# Meshtastic-DIY_v2.net
KiCad netlist of a schematic drawn in EAGLE
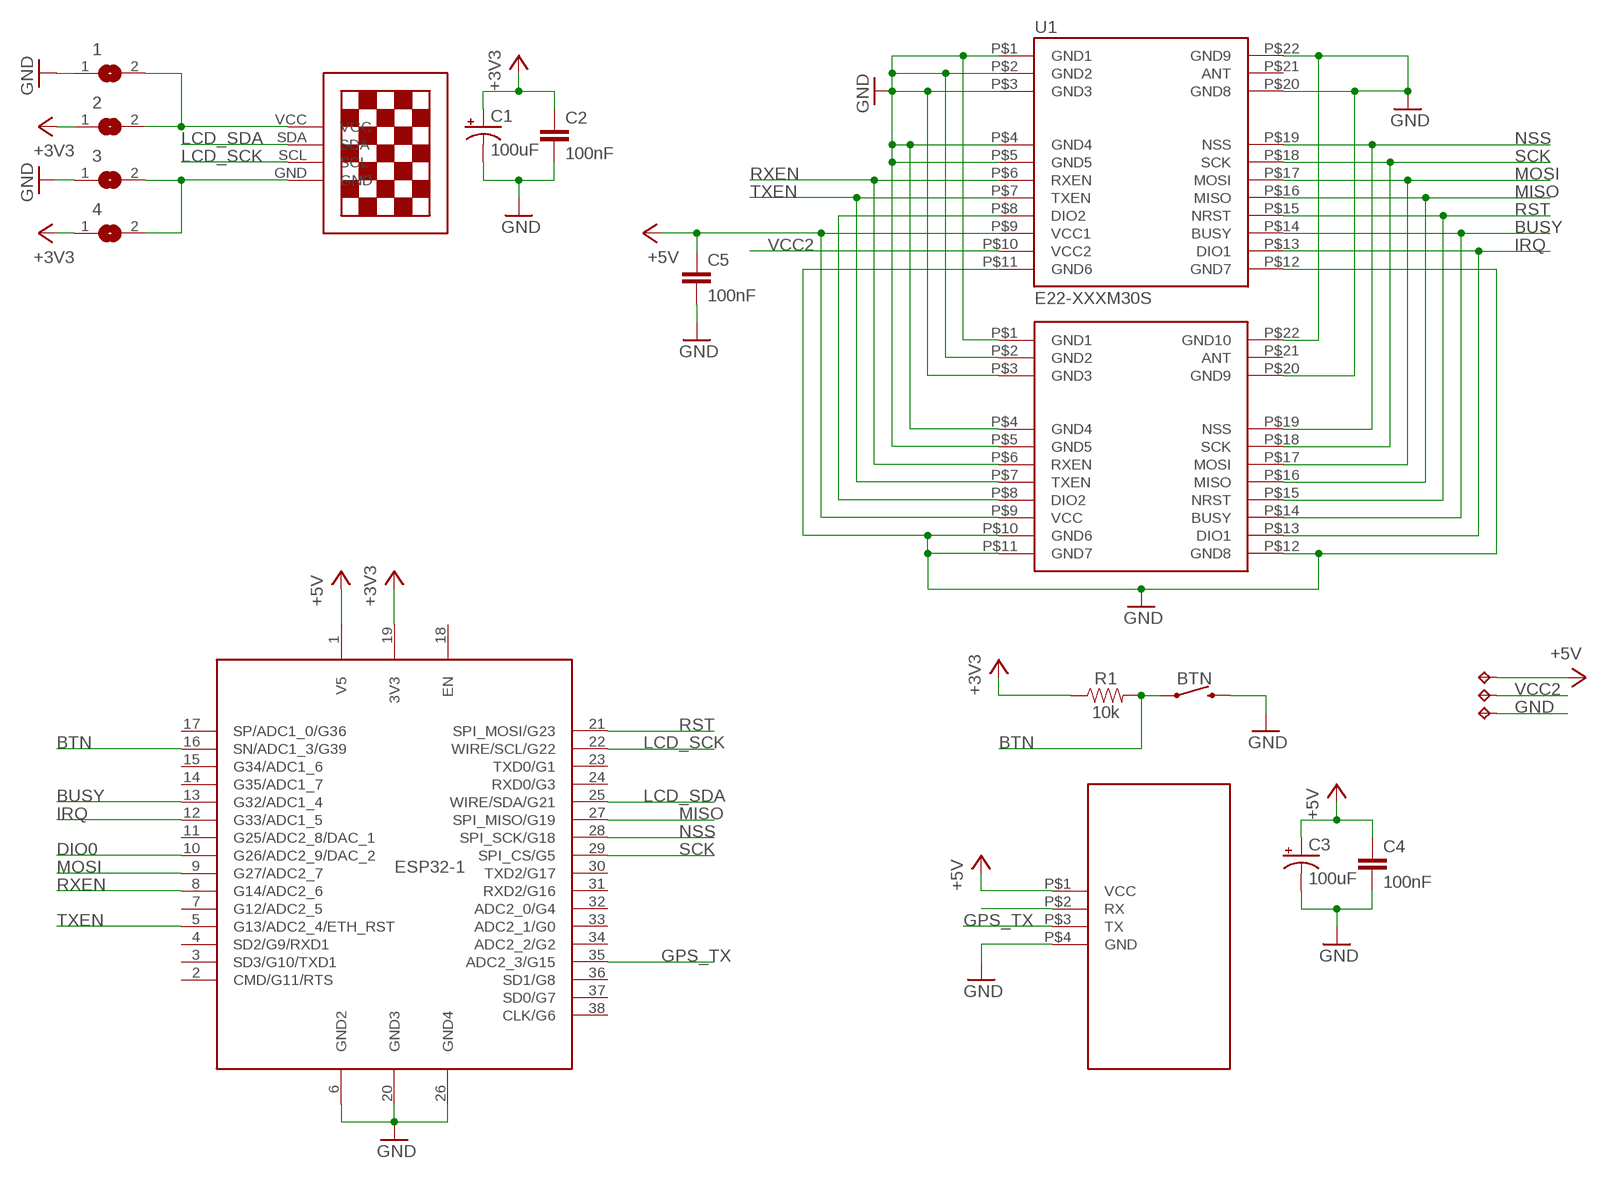
[diagram p0: schematic, sheet 1]

(export (version "E")
  (design (tool "Eeschema 10.0.6"))
  (components
    (comp (ref "1") (value "SJ") (footprint "eagle-import:SJ") (libsource (lib "eagle-import") (part "SJ")))
    (comp (ref "2") (value "SJ") (footprint "eagle-import:SJ") (libsource (lib "eagle-import") (part "SJ")))
    (comp (ref "3") (value "SJ") (footprint "eagle-import:SJ") (libsource (lib "eagle-import") (part "SJ")))
    (comp (ref "4") (value "SJ") (footprint "eagle-import:SJ") (libsource (lib "eagle-import") (part "SJ")))
    (comp (ref "BTN")
      (value "MOMENTARY-SWITCH-SPST-PTH-6.0MM")
      (footprint "eagle-import:TACTILE_SWITCH_PTH_6.0MM")
      (libsource (lib "eagle-import") (part "MOMENTARY-SWITCH-SPST-PTH-6.0MM"))
    )
    (comp (ref "C1")
      (value "100uF")
      (footprint "eagle-import:EIA7343")
      (libsource (lib "eagle-import") (part "100UF-POLAR-EIA7343-10V-10%(TANT)"))
    )
    (comp (ref "C2")
      (value "100nF")
      (footprint "eagle-import:0805")
      (libsource (lib "eagle-import") (part "0.33UF/330NF-0805-50V-10%"))
    )
    (comp (ref "C3")
      (value "100uF")
      (footprint "eagle-import:EIA7343")
      (libsource (lib "eagle-import") (part "100UF-POLAR-EIA7343-10V-10%(TANT)"))
    )
    (comp (ref "C4")
      (value "100nF")
      (footprint "eagle-import:0805")
      (libsource (lib "eagle-import") (part "0.33UF/330NF-0805-50V-10%"))
    )
    (comp (ref "C5")
      (value "100nF")
      (footprint "eagle-import:0805")
      (libsource (lib "eagle-import") (part "0.33UF/330NF-0805-50V-10%"))
    )
    (comp (ref "ESP32-1")
      (value "NODEMCU_ESP32_WROOM_32")
      (footprint "eagle-import:NODEMCU_ESP32_WROOM_32--38PINS")
      (libsource (lib "eagle-import") (part "NODEMCU_ESP32_WROOM_32"))
    )
    (comp (ref "R1")
      (value "10k")
      (footprint "eagle-import:1210")
      (libsource (lib "eagle-import") (part "0.1OHM-1210-1/2W-1%"))
    )
    (comp (ref "TP1")
      (value "TPTP14SQ")
      (footprint "eagle-import:TP14SQ")
      (libsource (lib "eagle-import") (part "TPTP14SQ"))
    )
    (comp (ref "TP2")
      (value "TPTP14SQ")
      (footprint "eagle-import:TP14SQ")
      (libsource (lib "eagle-import") (part "TPTP14SQ"))
    )
    (comp (ref "TP3")
      (value "TPTP14SQ")
      (footprint "eagle-import:TP14SQ")
      (libsource (lib "eagle-import") (part "TPTP14SQ"))
    )
    (comp (ref "U$1")
      (value "13\"OLED13\"OLED")
      (footprint "eagle-import:1.3_OLED")
      (libsource (lib "eagle-import") (part "13{dblquote}OLED13{dblquote}OLED"))
    )
    (comp (ref "U$2")
      (value "E22-XXXM22S")
      (footprint "eagle-import:E22-XXXM22S")
      (libsource (lib "eagle-import") (part "E22-XXXM22S"))
    )
    (comp (ref "U$3")
      (value "GPS-NEO")
      (footprint "eagle-import:GPS-NEO")
      (libsource (lib "eagle-import") (part "GPS-NEO"))
    )
    (comp (ref "U1")
      (value "E22-XXXM30S")
      (footprint "eagle-import:E22-XXXM30S")
      (libsource (lib "eagle-import") (part "E22-XXXM30S"))
    )
  )
  (nets
    (net (code "1") (name "+3V3") (class "Default")
      (node (ref "2") (pin "1") (pinfunction "1_1") (pintype "passive"))
      (node (ref "4") (pin "1") (pinfunction "1_1") (pintype "passive"))
      (node (ref "C1") (pin "A") (pinfunction "+_A") (pintype "passive"))
      (node (ref "C2") (pin "1") (pinfunction "1_1") (pintype "passive"))
      (node (ref "ESP32-1") (pin "19") (pinfunction "3V3_19") (pintype "power_in"))
      (node (ref "R1") (pin "1") (pinfunction "1_1") (pintype "passive"))
    )
    (net (code "2") (name "+5V") (class "Default")
      (node (ref "C3") (pin "A") (pinfunction "+_A") (pintype "passive"))
      (node (ref "C4") (pin "1") (pinfunction "1_1") (pintype "passive"))
      (node (ref "C5") (pin "1") (pinfunction "1_1") (pintype "passive"))
      (node (ref "ESP32-1") (pin "1") (pinfunction "V5_1") (pintype "power_in"))
      (node (ref "TP1") (pin "TP") (pinfunction "TP_TP") (pintype "input"))
      (node (ref "U$2") (pin "P$9") (pinfunction "VCC_P$9") (pintype "bidirectional"))
      (node (ref "U$3") (pin "P$1") (pinfunction "VCC_P$1") (pintype "bidirectional"))
      (node (ref "U1") (pin "P$9") (pinfunction "VCC1_P$9") (pintype "bidirectional"))
    )
    (net (code "3") (name "/BTN") (class "Default")
      (node (ref "BTN") (pin "1") (pinfunction "1_1") (pintype "passive"))
      (node (ref "ESP32-1") (pin "16") (pinfunction "SN/ADC1_3/G39_16") (pintype "bidirectional"))
      (node (ref "R1") (pin "2") (pinfunction "2_2") (pintype "passive"))
    )
    (net (code "4") (name "/BUSY") (class "Default")
      (node (ref "ESP32-1") (pin "13") (pinfunction "G32/ADC1_4_13") (pintype "bidirectional"))
      (node (ref "U$2") (pin "P$14") (pinfunction "BUSY_P$14") (pintype "bidirectional"))
      (node (ref "U1") (pin "P$14") (pinfunction "BUSY_P$14") (pintype "bidirectional"))
    )
    (net (code "5") (name "/CMD{slash}G11{slash}RTS") (class "Default")
      (node (ref "ESP32-1") (pin "2") (pinfunction "CMD/G11/RTS_2") (pintype "power_in"))
    )
    (net (code "6") (name "/DIO0") (class "Default")
      (node (ref "ESP32-1") (pin "10") (pinfunction "G26/ADC2_9/DAC_2_10") (pintype "bidirectional"))
    )
    (net (code "7") (name "/GPS_TX") (class "Default")
      (node (ref "ESP32-1") (pin "35") (pinfunction "ADC2_3/G15_35") (pintype "bidirectional"))
      (node (ref "U$3") (pin "P$3") (pinfunction "TX_P$3") (pintype "bidirectional"))
    )
    (net (code "8") (name "/IRQ") (class "Default")
      (node (ref "ESP32-1") (pin "12") (pinfunction "G33/ADC1_5_12") (pintype "bidirectional"))
      (node (ref "U$2") (pin "P$13") (pinfunction "DIO1_P$13") (pintype "bidirectional"))
      (node (ref "U1") (pin "P$13") (pinfunction "DIO1_P$13") (pintype "bidirectional"))
    )
    (net (code "9") (name "/LCD_SCK") (class "Default")
      (node (ref "ESP32-1") (pin "22") (pinfunction "WIRE/SCL/G22_22") (pintype "bidirectional"))
      (node (ref "U$1") (pin "SCL") (pinfunction "SCL_SCL") (pintype "bidirectional"))
    )
    (net (code "10") (name "/LCD_SDA") (class "Default")
      (node (ref "ESP32-1") (pin "25") (pinfunction "WIRE/SDA/G21_25") (pintype "bidirectional"))
      (node (ref "U$1") (pin "SDA") (pinfunction "SDA_SDA") (pintype "bidirectional"))
    )
    (net (code "11") (name "/MISO") (class "Default")
      (node (ref "ESP32-1") (pin "27") (pinfunction "SPI_MISO/G19_27") (pintype "bidirectional"))
      (node (ref "U$2") (pin "P$16") (pinfunction "MISO_P$16") (pintype "bidirectional"))
      (node (ref "U1") (pin "P$16") (pinfunction "MISO_P$16") (pintype "bidirectional"))
    )
    (net (code "12") (name "/MOSI") (class "Default")
      (node (ref "ESP32-1") (pin "9") (pinfunction "G27/ADC2_7_9") (pintype "bidirectional"))
      (node (ref "U$2") (pin "P$17") (pinfunction "MOSI_P$17") (pintype "bidirectional"))
      (node (ref "U1") (pin "P$17") (pinfunction "MOSI_P$17") (pintype "bidirectional"))
    )
    (net (code "13") (name "/NSS") (class "Default")
      (node (ref "ESP32-1") (pin "28") (pinfunction "SPI_SCK/G18_28") (pintype "bidirectional"))
      (node (ref "U$2") (pin "P$19") (pinfunction "NSS_P$19") (pintype "bidirectional"))
      (node (ref "U1") (pin "P$19") (pinfunction "NSS_P$19") (pintype "bidirectional"))
    )
    (net (code "14") (name "/RST") (class "Default")
      (node (ref "ESP32-1") (pin "21") (pinfunction "SPI_MOSI/G23_21") (pintype "bidirectional"))
      (node (ref "U$2") (pin "P$15") (pinfunction "NRST_P$15") (pintype "bidirectional"))
      (node (ref "U1") (pin "P$15") (pinfunction "NRST_P$15") (pintype "bidirectional"))
    )
    (net (code "15") (name "/RXEN") (class "Default")
      (node (ref "ESP32-1") (pin "8") (pinfunction "G14/ADC2_6_8") (pintype "bidirectional"))
      (node (ref "U$2") (pin "P$6") (pinfunction "RXEN_P$6") (pintype "bidirectional"))
      (node (ref "U1") (pin "P$6") (pinfunction "RXEN_P$6") (pintype "bidirectional"))
    )
    (net (code "16") (name "/SCK") (class "Default")
      (node (ref "ESP32-1") (pin "29") (pinfunction "SPI_CS/G5_29") (pintype "bidirectional"))
      (node (ref "U$2") (pin "P$18") (pinfunction "SCK_P$18") (pintype "bidirectional"))
      (node (ref "U1") (pin "P$18") (pinfunction "SCK_P$18") (pintype "bidirectional"))
    )
    (net (code "17") (name "/TXEN") (class "Default")
      (node (ref "ESP32-1") (pin "5") (pinfunction "G13/ADC2_4/ETH_RST_5") (pintype "bidirectional"))
      (node (ref "U$2") (pin "P$7") (pinfunction "TXEN_P$7") (pintype "bidirectional"))
      (node (ref "U1") (pin "P$7") (pinfunction "TXEN_P$7") (pintype "bidirectional"))
    )
    (net (code "18") (name "/VCC2") (class "Default")
      (node (ref "TP2") (pin "TP") (pinfunction "TP_TP") (pintype "input"))
      (node (ref "U1") (pin "P$10") (pinfunction "VCC2_P$10") (pintype "bidirectional"))
    )
    (net (code "19") (name "GND") (class "Default")
      (node (ref "1") (pin "1") (pinfunction "1_1") (pintype "passive"))
      (node (ref "3") (pin "1") (pinfunction "1_1") (pintype "passive"))
      (node (ref "BTN") (pin "3") (pinfunction "2_3") (pintype "passive"))
      (node (ref "C1") (pin "C") (pinfunction "-_C") (pintype "passive"))
      (node (ref "C2") (pin "2") (pinfunction "2_2") (pintype "passive"))
      (node (ref "C3") (pin "C") (pinfunction "-_C") (pintype "passive"))
      (node (ref "C4") (pin "2") (pinfunction "2_2") (pintype "passive"))
      (node (ref "C5") (pin "2") (pinfunction "2_2") (pintype "passive"))
      (node (ref "ESP32-1") (pin "20") (pinfunction "GND3_20") (pintype "power_in"))
      (node (ref "ESP32-1") (pin "26") (pinfunction "GND4_26") (pintype "power_in"))
      (node (ref "ESP32-1") (pin "6") (pinfunction "GND2_6") (pintype "power_in"))
      (node (ref "TP3") (pin "TP") (pinfunction "TP_TP") (pintype "input"))
      (node (ref "U$2") (pin "P$1") (pinfunction "GND1_P$1") (pintype "bidirectional"))
      (node (ref "U$2") (pin "P$10") (pinfunction "GND6_P$10") (pintype "bidirectional"))
      (node (ref "U$2") (pin "P$11") (pinfunction "GND7_P$11") (pintype "bidirectional"))
      (node (ref "U$2") (pin "P$12") (pinfunction "GND8_P$12") (pintype "bidirectional"))
      (node (ref "U$2") (pin "P$2") (pinfunction "GND2_P$2") (pintype "bidirectional"))
      (node (ref "U$2") (pin "P$20") (pinfunction "GND9_P$20") (pintype "bidirectional"))
      (node (ref "U$2") (pin "P$22") (pinfunction "GND10_P$22") (pintype "bidirectional"))
      (node (ref "U$2") (pin "P$3") (pinfunction "GND3_P$3") (pintype "bidirectional"))
      (node (ref "U$2") (pin "P$4") (pinfunction "GND4_P$4") (pintype "bidirectional"))
      (node (ref "U$2") (pin "P$5") (pinfunction "GND5_P$5") (pintype "bidirectional"))
      (node (ref "U$3") (pin "P$4") (pinfunction "GND_P$4") (pintype "bidirectional"))
      (node (ref "U1") (pin "P$1") (pinfunction "GND1_P$1") (pintype "bidirectional"))
      (node (ref "U1") (pin "P$11") (pinfunction "GND6_P$11") (pintype "bidirectional"))
      (node (ref "U1") (pin "P$12") (pinfunction "GND7_P$12") (pintype "bidirectional"))
      (node (ref "U1") (pin "P$2") (pinfunction "GND2_P$2") (pintype "bidirectional"))
      (node (ref "U1") (pin "P$20") (pinfunction "GND8_P$20") (pintype "bidirectional"))
      (node (ref "U1") (pin "P$22") (pinfunction "GND9_P$22") (pintype "bidirectional"))
      (node (ref "U1") (pin "P$3") (pinfunction "GND3_P$3") (pintype "bidirectional"))
      (node (ref "U1") (pin "P$4") (pinfunction "GND4_P$4") (pintype "bidirectional"))
      (node (ref "U1") (pin "P$5") (pinfunction "GND5_P$5") (pintype "bidirectional"))
    )
    (net (code "20") (name "Net-(1-Pad2)") (class "Default")
      (node (ref "1") (pin "2") (pinfunction "2_2") (pintype "passive"))
      (node (ref "2") (pin "2") (pinfunction "2_2") (pintype "passive"))
      (node (ref "U$1") (pin "VCC") (pinfunction "VCC_VCC") (pintype "bidirectional"))
    )
    (net (code "21") (name "Net-(3-Pad2)") (class "Default")
      (node (ref "3") (pin "2") (pinfunction "2_2") (pintype "passive"))
      (node (ref "4") (pin "2") (pinfunction "2_2") (pintype "passive"))
      (node (ref "U$1") (pin "GND") (pinfunction "GND_GND") (pintype "bidirectional"))
    )
    (net (code "22") (name "Net-(U$2-DIO2)") (class "Default")
      (node (ref "U$2") (pin "P$8") (pinfunction "DIO2_P$8") (pintype "bidirectional"))
      (node (ref "U1") (pin "P$8") (pinfunction "DIO2_P$8") (pintype "bidirectional"))
    )
    (net (code "23") (name "unconnected-(ESP32-1-ADC2_0{slash}G4-Pad32)") (class "Default")
      (node (ref "ESP32-1") (pin "32") (pinfunction "ADC2_0/G4_32") (pintype "bidirectional"))
    )
    (net (code "24") (name "unconnected-(ESP32-1-ADC2_1{slash}G0-Pad33)") (class "Default")
      (node (ref "ESP32-1") (pin "33") (pinfunction "ADC2_1/G0_33") (pintype "bidirectional"))
    )
    (net (code "25") (name "unconnected-(ESP32-1-ADC2_2{slash}G2-Pad34)") (class "Default")
      (node (ref "ESP32-1") (pin "34") (pinfunction "ADC2_2/G2_34") (pintype "bidirectional"))
    )
    (net (code "26") (name "unconnected-(ESP32-1-CLK{slash}G6-Pad38)") (class "Default")
      (node (ref "ESP32-1") (pin "38") (pinfunction "CLK/G6_38") (pintype "bidirectional"))
    )
    (net (code "27") (name "unconnected-(ESP32-1-EN-Pad18)") (class "Default")
      (node (ref "ESP32-1") (pin "18") (pinfunction "EN_18") (pintype "bidirectional"))
    )
    (net (code "28") (name "unconnected-(ESP32-1-G12{slash}ADC2_5-Pad7)") (class "Default")
      (node (ref "ESP32-1") (pin "7") (pinfunction "G12/ADC2_5_7") (pintype "bidirectional"))
    )
    (net (code "29") (name "unconnected-(ESP32-1-G25{slash}ADC2_8{slash}DAC_1-Pad11)") (class "Default")
      (node (ref "ESP32-1") (pin "11") (pinfunction "G25/ADC2_8/DAC_1_11") (pintype "bidirectional"))
    )
    (net (code "30") (name "unconnected-(ESP32-1-G34{slash}ADC1_6-Pad15)") (class "Default")
      (node (ref "ESP32-1") (pin "15") (pinfunction "G34/ADC1_6_15") (pintype "bidirectional"))
    )
    (net (code "31") (name "unconnected-(ESP32-1-G35{slash}ADC1_7-Pad14)") (class "Default")
      (node (ref "ESP32-1") (pin "14") (pinfunction "G35/ADC1_7_14") (pintype "bidirectional"))
    )
    (net (code "32") (name "unconnected-(ESP32-1-RXD0{slash}G3-Pad24)") (class "Default")
      (node (ref "ESP32-1") (pin "24") (pinfunction "RXD0/G3_24") (pintype "bidirectional"))
    )
    (net (code "33") (name "unconnected-(ESP32-1-RXD2{slash}G16-Pad31)") (class "Default")
      (node (ref "ESP32-1") (pin "31") (pinfunction "RXD2/G16_31") (pintype "bidirectional"))
    )
    (net (code "34") (name "unconnected-(ESP32-1-SD0{slash}G7-Pad37)") (class "Default")
      (node (ref "ESP32-1") (pin "37") (pinfunction "SD0/G7_37") (pintype "bidirectional"))
    )
    (net (code "35") (name "unconnected-(ESP32-1-SD1{slash}G8-Pad36)") (class "Default")
      (node (ref "ESP32-1") (pin "36") (pinfunction "SD1/G8_36") (pintype "bidirectional"))
    )
    (net (code "36") (name "unconnected-(ESP32-1-SD2{slash}G9{slash}RXD1-Pad4)") (class "Default")
      (node (ref "ESP32-1") (pin "4") (pinfunction "SD2/G9/RXD1_4") (pintype "bidirectional"))
    )
    (net (code "37") (name "unconnected-(ESP32-1-SD3{slash}G10{slash}TXD1-Pad3)") (class "Default")
      (node (ref "ESP32-1") (pin "3") (pinfunction "SD3/G10/TXD1_3") (pintype "bidirectional"))
    )
    (net (code "38") (name "unconnected-(ESP32-1-SP{slash}ADC1_0{slash}G36-Pad17)") (class "Default")
      (node (ref "ESP32-1") (pin "17") (pinfunction "SP/ADC1_0/G36_17") (pintype "bidirectional"))
    )
    (net (code "39") (name "unconnected-(ESP32-1-TXD0{slash}G1-Pad23)") (class "Default")
      (node (ref "ESP32-1") (pin "23") (pinfunction "TXD0/G1_23") (pintype "bidirectional"))
    )
    (net (code "40") (name "unconnected-(ESP32-1-TXD2{slash}G17-Pad30)") (class "Default")
      (node (ref "ESP32-1") (pin "30") (pinfunction "TXD2/G17_30") (pintype "bidirectional"))
    )
    (net (code "41") (name "unconnected-(U$2-ANT-PadP$21)") (class "Default")
      (node (ref "U$2") (pin "P$21") (pinfunction "ANT_P$21") (pintype "bidirectional"))
    )
    (net (code "42") (name "unconnected-(U$3-RX-PadP$2)") (class "Default")
      (node (ref "U$3") (pin "P$2") (pinfunction "RX_P$2") (pintype "bidirectional"))
    )
    (net (code "43") (name "unconnected-(U1-ANT-PadP$21)") (class "Default")
      (node (ref "U1") (pin "P$21") (pinfunction "ANT_P$21") (pintype "bidirectional"))
    )
  )
)
